# wiimote_sensor.net
KiCad netlist of a schematic drawn in EAGLE
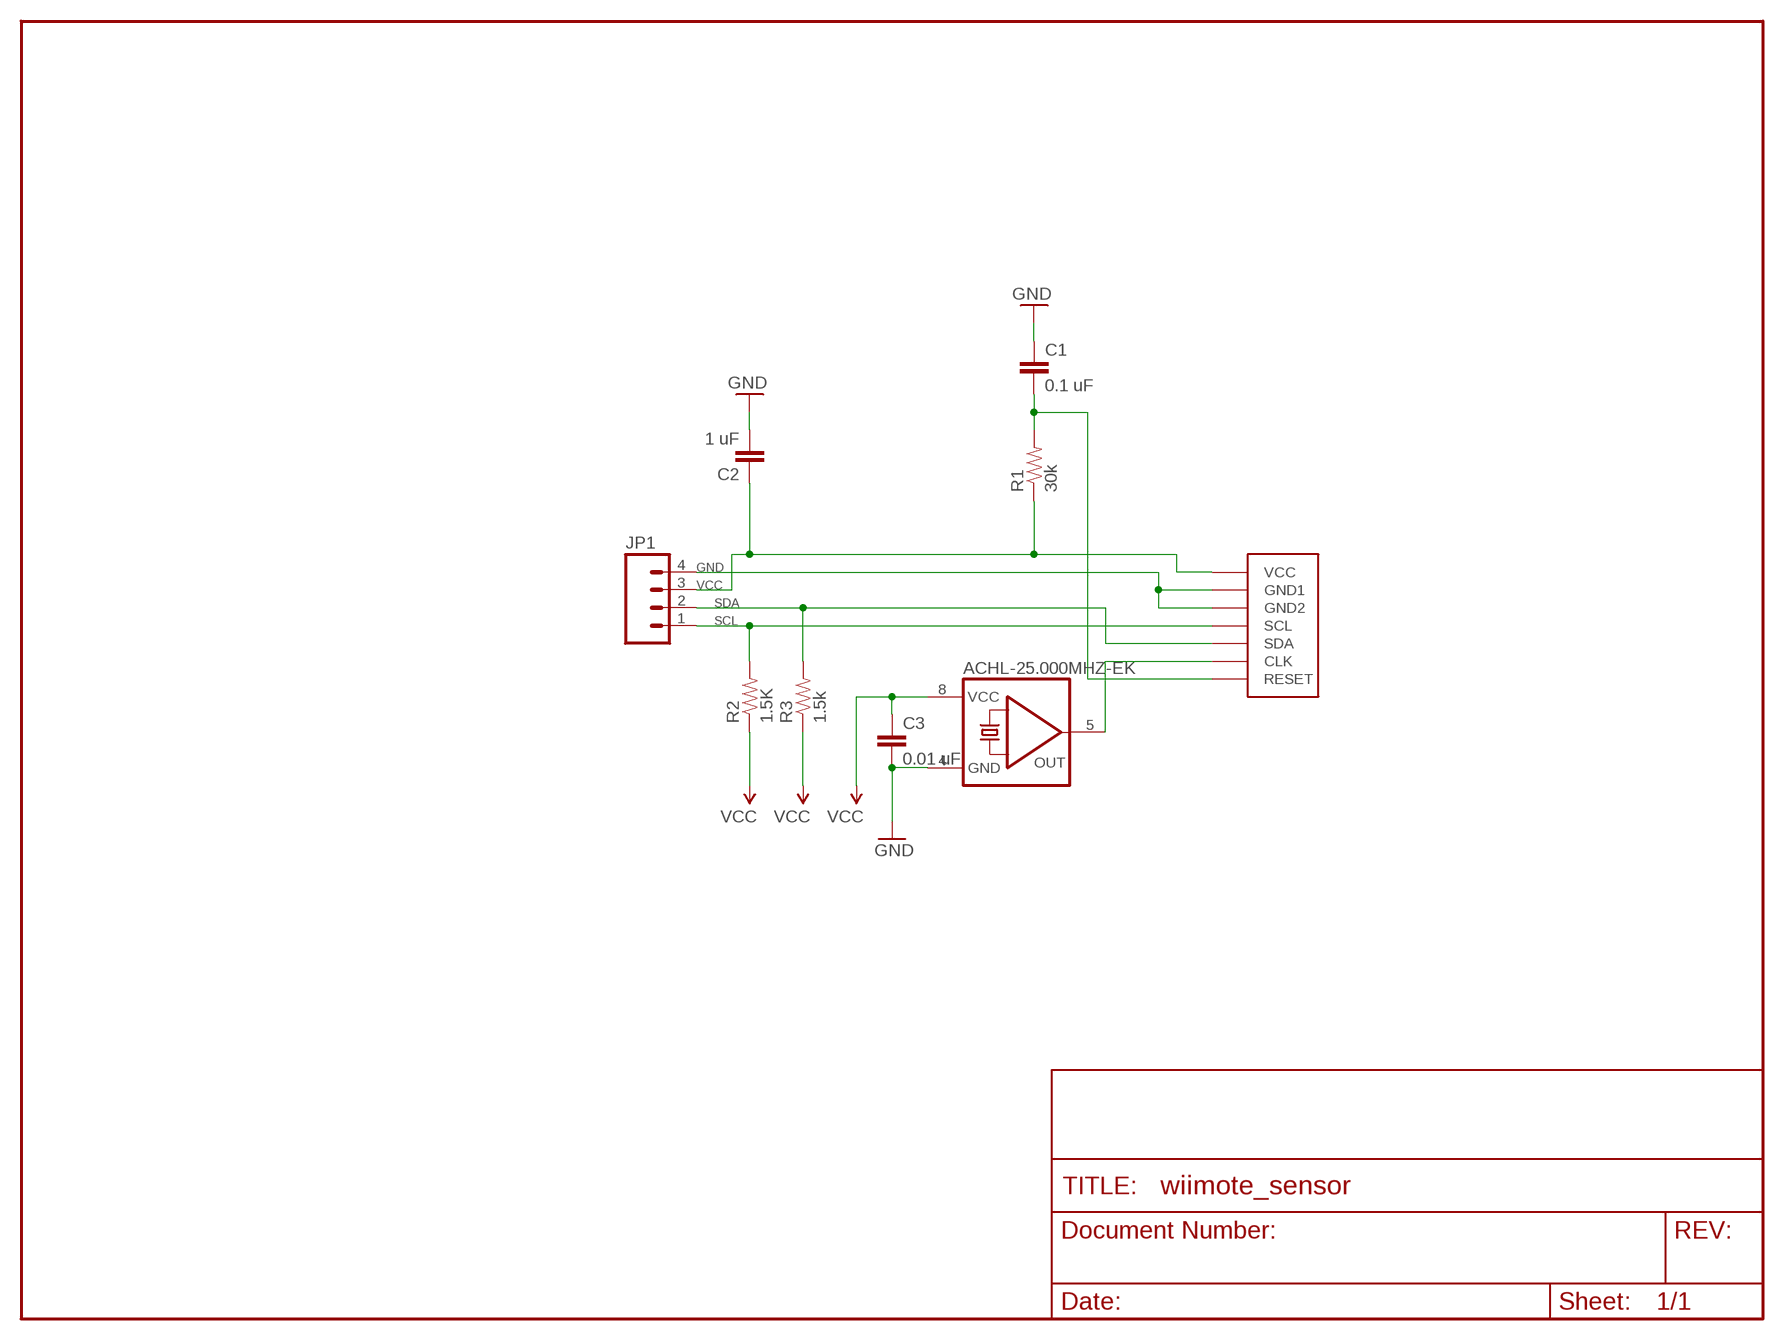
[diagram p0: schematic, sheet 1]

(export (version "E")
  (design (tool "Eeschema 10.0.6"))
  (components
    (comp (ref "ACHL-25.000MHZ-EK")
      (value "QG5460")
      (footprint "eagle-import:DIL08S")
      (libsource (lib "eagle-import") (part "QG5460"))
    )
    (comp (ref "C1")
      (value "0.1 uF")
      (footprint "eagle-import:0805")
      (libsource (lib "eagle-import") (part "CAP0805"))
    )
    (comp (ref "C2")
      (value "1 uF")
      (footprint "eagle-import:0805")
      (libsource (lib "eagle-import") (part "CAP0805"))
    )
    (comp (ref "C3")
      (value "0.01 uF")
      (footprint "eagle-import:0805")
      (libsource (lib "eagle-import") (part "CAP0805"))
    )
    (comp (ref "JP1")
      (value "M04POLAR")
      (footprint "eagle-import:MOLEX-1X4")
      (libsource (lib "eagle-import") (part "M04POLAR"))
    )
    (comp (ref "R1")
      (value "30k")
      (footprint "eagle-import:0805")
      (libsource (lib "eagle-import") (part "RESISTOR0805-RES"))
    )
    (comp (ref "R2")
      (value "1.5K")
      (footprint "eagle-import:0805")
      (libsource (lib "eagle-import") (part "RESISTOR0805-RES"))
    )
    (comp (ref "R3")
      (value "1.5k")
      (footprint "eagle-import:0805")
      (libsource (lib "eagle-import") (part "RESISTOR0805-RES"))
    )
    (comp (ref "U$1")
      (value "PIXART")
      (footprint "eagle-import:PIXART")
      (libsource (lib "eagle-import") (part "PIXART"))
    )
  )
  (nets
    (net (code "1") (name "/SCL") (class "Default")
      (node (ref "JP1") (pin "1") (pinfunction "1_1") (pintype "passive"))
      (node (ref "R2") (pin "2") (pinfunction "2_2") (pintype "passive"))
      (node (ref "U$1") (pin "5") (pinfunction "SCL_5") (pintype "bidirectional"))
    )
    (net (code "2") (name "/SDA") (class "Default")
      (node (ref "JP1") (pin "2") (pinfunction "2_2") (pintype "passive"))
      (node (ref "R3") (pin "2") (pinfunction "2_2") (pintype "passive"))
      (node (ref "U$1") (pin "6") (pinfunction "SDA_6") (pintype "bidirectional"))
    )
    (net (code "3") (name "GND") (class "Default")
      (node (ref "ACHL-25.000MHZ-EK") (pin "4") (pinfunction "GND_4") (pintype "power_in"))
      (node (ref "C1") (pin "1") (pinfunction "1_1") (pintype "passive"))
      (node (ref "C2") (pin "2") (pinfunction "2_2") (pintype "passive"))
      (node (ref "C3") (pin "2") (pinfunction "2_2") (pintype "passive"))
      (node (ref "JP1") (pin "4") (pinfunction "4_4") (pintype "passive"))
      (node (ref "U$1") (pin "2") (pinfunction "GND1_2") (pintype "bidirectional"))
      (node (ref "U$1") (pin "3") (pinfunction "GND2_3") (pintype "bidirectional"))
    )
    (net (code "4") (name "Net-(ACHL-25.000MHZ-EK-OUT)") (class "Default")
      (node (ref "ACHL-25.000MHZ-EK") (pin "5") (pinfunction "OUT_5") (pintype "output"))
      (node (ref "U$1") (pin "7") (pinfunction "CLK_7") (pintype "bidirectional"))
    )
    (net (code "5") (name "Net-(U$1-RESET)") (class "Default")
      (node (ref "C1") (pin "2") (pinfunction "2_2") (pintype "passive"))
      (node (ref "R1") (pin "2") (pinfunction "2_2") (pintype "passive"))
      (node (ref "U$1") (pin "8") (pinfunction "RESET_8") (pintype "bidirectional"))
    )
    (net (code "6") (name "VCC") (class "Default")
      (node (ref "ACHL-25.000MHZ-EK") (pin "8") (pinfunction "VCC_8") (pintype "power_in"))
      (node (ref "C2") (pin "1") (pinfunction "1_1") (pintype "passive"))
      (node (ref "C3") (pin "1") (pinfunction "1_1") (pintype "passive"))
      (node (ref "JP1") (pin "3") (pinfunction "3_3") (pintype "passive"))
      (node (ref "R1") (pin "1") (pinfunction "1_1") (pintype "passive"))
      (node (ref "R2") (pin "1") (pinfunction "1_1") (pintype "passive"))
      (node (ref "R3") (pin "1") (pinfunction "1_1") (pintype "passive"))
      (node (ref "U$1") (pin "1") (pinfunction "VCC_1") (pintype "bidirectional"))
    )
  )
)
